# ADDR_ADDR_1.net
KiCad netlist of a schematic drawn in EAGLE
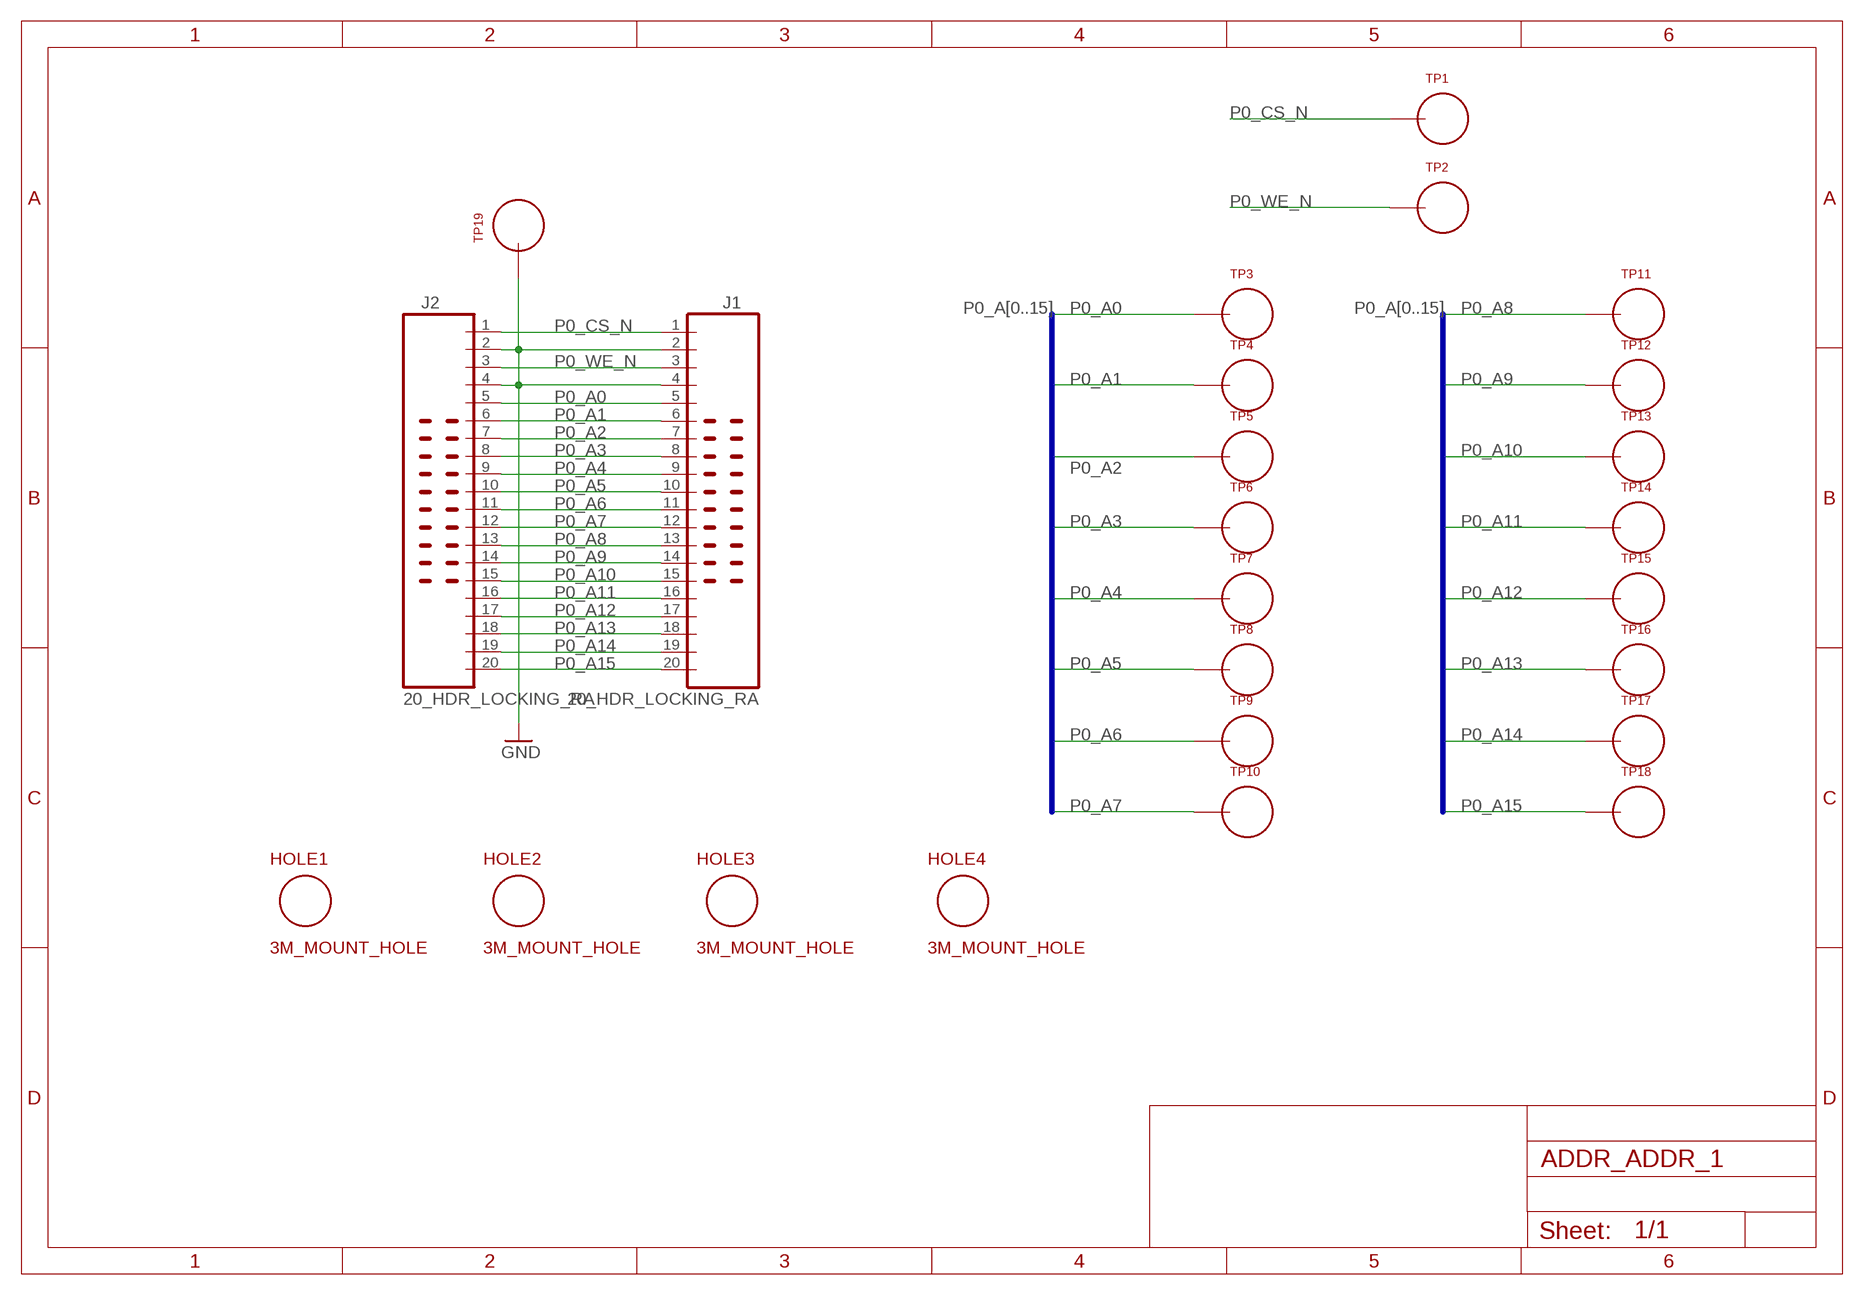
[diagram p0: schematic, sheet 1]

(export (version "E")
  (design (tool "Eeschema 10.0.6"))
  (components
    (comp (ref "HOLE1")
      (value "3M_MOUNT_HOLE")
      (footprint "eagle-import:3M_HOLE")
      (libsource (lib "eagle-import") (part "3M_MOUNT_HOLE"))
    )
    (comp (ref "HOLE2")
      (value "3M_MOUNT_HOLE")
      (footprint "eagle-import:3M_HOLE")
      (libsource (lib "eagle-import") (part "3M_MOUNT_HOLE"))
    )
    (comp (ref "HOLE3")
      (value "3M_MOUNT_HOLE")
      (footprint "eagle-import:3M_HOLE")
      (libsource (lib "eagle-import") (part "3M_MOUNT_HOLE"))
    )
    (comp (ref "HOLE4")
      (value "3M_MOUNT_HOLE")
      (footprint "eagle-import:3M_HOLE")
      (libsource (lib "eagle-import") (part "3M_MOUNT_HOLE"))
    )
    (comp (ref "J1")
      (value "20_HDR_LOCKING_RA")
      (footprint "eagle-import:20_HDR_LOCKING_RA")
      (libsource (lib "eagle-import") (part "20_HDR_LOCKING_RA"))
    )
    (comp (ref "J2")
      (value "20_HDR_LOCKING_RA")
      (footprint "eagle-import:20_HDR_LOCKING_RA")
      (libsource (lib "eagle-import") (part "20_HDR_LOCKING_RA"))
    )
    (comp (ref "TP1")
      (value "TEST_LOOP")
      (footprint "eagle-import:TEST_LOOP")
      (libsource (lib "eagle-import") (part "TEST_LOOP"))
    )
    (comp (ref "TP2")
      (value "TEST_LOOP")
      (footprint "eagle-import:TEST_LOOP")
      (libsource (lib "eagle-import") (part "TEST_LOOP"))
    )
    (comp (ref "TP3")
      (value "TEST_LOOP")
      (footprint "eagle-import:TEST_LOOP")
      (libsource (lib "eagle-import") (part "TEST_LOOP"))
    )
    (comp (ref "TP4")
      (value "TEST_LOOP")
      (footprint "eagle-import:TEST_LOOP")
      (libsource (lib "eagle-import") (part "TEST_LOOP"))
    )
    (comp (ref "TP5")
      (value "TEST_LOOP")
      (footprint "eagle-import:TEST_LOOP")
      (libsource (lib "eagle-import") (part "TEST_LOOP"))
    )
    (comp (ref "TP6")
      (value "TEST_LOOP")
      (footprint "eagle-import:TEST_LOOP")
      (libsource (lib "eagle-import") (part "TEST_LOOP"))
    )
    (comp (ref "TP7")
      (value "TEST_LOOP")
      (footprint "eagle-import:TEST_LOOP")
      (libsource (lib "eagle-import") (part "TEST_LOOP"))
    )
    (comp (ref "TP8")
      (value "TEST_LOOP")
      (footprint "eagle-import:TEST_LOOP")
      (libsource (lib "eagle-import") (part "TEST_LOOP"))
    )
    (comp (ref "TP9")
      (value "TEST_LOOP")
      (footprint "eagle-import:TEST_LOOP")
      (libsource (lib "eagle-import") (part "TEST_LOOP"))
    )
    (comp (ref "TP10")
      (value "TEST_LOOP")
      (footprint "eagle-import:TEST_LOOP")
      (libsource (lib "eagle-import") (part "TEST_LOOP"))
    )
    (comp (ref "TP11")
      (value "TEST_LOOP")
      (footprint "eagle-import:TEST_LOOP")
      (libsource (lib "eagle-import") (part "TEST_LOOP"))
    )
    (comp (ref "TP12")
      (value "TEST_LOOP")
      (footprint "eagle-import:TEST_LOOP")
      (libsource (lib "eagle-import") (part "TEST_LOOP"))
    )
    (comp (ref "TP13")
      (value "TEST_LOOP")
      (footprint "eagle-import:TEST_LOOP")
      (libsource (lib "eagle-import") (part "TEST_LOOP"))
    )
    (comp (ref "TP14")
      (value "TEST_LOOP")
      (footprint "eagle-import:TEST_LOOP")
      (libsource (lib "eagle-import") (part "TEST_LOOP"))
    )
    (comp (ref "TP15")
      (value "TEST_LOOP")
      (footprint "eagle-import:TEST_LOOP")
      (libsource (lib "eagle-import") (part "TEST_LOOP"))
    )
    (comp (ref "TP16")
      (value "TEST_LOOP")
      (footprint "eagle-import:TEST_LOOP")
      (libsource (lib "eagle-import") (part "TEST_LOOP"))
    )
    (comp (ref "TP17")
      (value "TEST_LOOP")
      (footprint "eagle-import:TEST_LOOP")
      (libsource (lib "eagle-import") (part "TEST_LOOP"))
    )
    (comp (ref "TP18")
      (value "TEST_LOOP")
      (footprint "eagle-import:TEST_LOOP")
      (libsource (lib "eagle-import") (part "TEST_LOOP"))
    )
    (comp (ref "TP19")
      (value "TEST_LOOP")
      (footprint "eagle-import:TEST_LOOP")
      (libsource (lib "eagle-import") (part "TEST_LOOP"))
    )
  )
  (nets
    (net (code "1") (name "/P0_A0") (class "Default")
      (node (ref "J1") (pin "5") (pinfunction "5_5") (pintype "bidirectional"))
      (node (ref "J2") (pin "5") (pinfunction "5_5") (pintype "bidirectional"))
      (node (ref "TP3") (pin "P$1") (pinfunction "P$1_P$1") (pintype "bidirectional"))
    )
    (net (code "2") (name "/P0_A1") (class "Default")
      (node (ref "J1") (pin "6") (pinfunction "6_6") (pintype "bidirectional"))
      (node (ref "J2") (pin "6") (pinfunction "6_6") (pintype "bidirectional"))
      (node (ref "TP4") (pin "P$1") (pinfunction "P$1_P$1") (pintype "bidirectional"))
    )
    (net (code "3") (name "/P0_A2") (class "Default")
      (node (ref "J1") (pin "7") (pinfunction "7_7") (pintype "bidirectional"))
      (node (ref "J2") (pin "7") (pinfunction "7_7") (pintype "bidirectional"))
      (node (ref "TP5") (pin "P$1") (pinfunction "P$1_P$1") (pintype "bidirectional"))
    )
    (net (code "4") (name "/P0_A3") (class "Default")
      (node (ref "J1") (pin "8") (pinfunction "8_8") (pintype "bidirectional"))
      (node (ref "J2") (pin "8") (pinfunction "8_8") (pintype "bidirectional"))
      (node (ref "TP6") (pin "P$1") (pinfunction "P$1_P$1") (pintype "bidirectional"))
    )
    (net (code "5") (name "/P0_A4") (class "Default")
      (node (ref "J1") (pin "9") (pinfunction "9_9") (pintype "bidirectional"))
      (node (ref "J2") (pin "9") (pinfunction "9_9") (pintype "bidirectional"))
      (node (ref "TP7") (pin "P$1") (pinfunction "P$1_P$1") (pintype "bidirectional"))
    )
    (net (code "6") (name "/P0_A5") (class "Default")
      (node (ref "J1") (pin "10") (pinfunction "10_10") (pintype "bidirectional"))
      (node (ref "J2") (pin "10") (pinfunction "10_10") (pintype "bidirectional"))
      (node (ref "TP8") (pin "P$1") (pinfunction "P$1_P$1") (pintype "bidirectional"))
    )
    (net (code "7") (name "/P0_A6") (class "Default")
      (node (ref "J1") (pin "11") (pinfunction "11_11") (pintype "bidirectional"))
      (node (ref "J2") (pin "11") (pinfunction "11_11") (pintype "bidirectional"))
      (node (ref "TP9") (pin "P$1") (pinfunction "P$1_P$1") (pintype "bidirectional"))
    )
    (net (code "8") (name "/P0_A7") (class "Default")
      (node (ref "J1") (pin "12") (pinfunction "12_12") (pintype "bidirectional"))
      (node (ref "J2") (pin "12") (pinfunction "12_12") (pintype "bidirectional"))
      (node (ref "TP10") (pin "P$1") (pinfunction "P$1_P$1") (pintype "bidirectional"))
    )
    (net (code "9") (name "/P0_A8") (class "Default")
      (node (ref "J1") (pin "13") (pinfunction "13_13") (pintype "bidirectional"))
      (node (ref "J2") (pin "13") (pinfunction "13_13") (pintype "bidirectional"))
      (node (ref "TP11") (pin "P$1") (pinfunction "P$1_P$1") (pintype "bidirectional"))
    )
    (net (code "10") (name "/P0_A9") (class "Default")
      (node (ref "J1") (pin "14") (pinfunction "14_14") (pintype "bidirectional"))
      (node (ref "J2") (pin "14") (pinfunction "14_14") (pintype "bidirectional"))
      (node (ref "TP12") (pin "P$1") (pinfunction "P$1_P$1") (pintype "bidirectional"))
    )
    (net (code "11") (name "/P0_A10") (class "Default")
      (node (ref "J1") (pin "15") (pinfunction "15_15") (pintype "bidirectional"))
      (node (ref "J2") (pin "15") (pinfunction "15_15") (pintype "bidirectional"))
      (node (ref "TP13") (pin "P$1") (pinfunction "P$1_P$1") (pintype "bidirectional"))
    )
    (net (code "12") (name "/P0_A11") (class "Default")
      (node (ref "J1") (pin "16") (pinfunction "16_16") (pintype "bidirectional"))
      (node (ref "J2") (pin "16") (pinfunction "16_16") (pintype "bidirectional"))
      (node (ref "TP14") (pin "P$1") (pinfunction "P$1_P$1") (pintype "bidirectional"))
    )
    (net (code "13") (name "/P0_A12") (class "Default")
      (node (ref "J1") (pin "17") (pinfunction "17_17") (pintype "bidirectional"))
      (node (ref "J2") (pin "17") (pinfunction "17_17") (pintype "bidirectional"))
      (node (ref "TP15") (pin "P$1") (pinfunction "P$1_P$1") (pintype "bidirectional"))
    )
    (net (code "14") (name "/P0_A13") (class "Default")
      (node (ref "J1") (pin "18") (pinfunction "18_18") (pintype "bidirectional"))
      (node (ref "J2") (pin "18") (pinfunction "18_18") (pintype "bidirectional"))
      (node (ref "TP16") (pin "P$1") (pinfunction "P$1_P$1") (pintype "bidirectional"))
    )
    (net (code "15") (name "/P0_A14") (class "Default")
      (node (ref "J1") (pin "19") (pinfunction "19_19") (pintype "bidirectional"))
      (node (ref "J2") (pin "19") (pinfunction "19_19") (pintype "bidirectional"))
      (node (ref "TP17") (pin "P$1") (pinfunction "P$1_P$1") (pintype "bidirectional"))
    )
    (net (code "16") (name "/P0_A15") (class "Default")
      (node (ref "J1") (pin "20") (pinfunction "20_20") (pintype "bidirectional"))
      (node (ref "J2") (pin "20") (pinfunction "20_20") (pintype "bidirectional"))
      (node (ref "TP18") (pin "P$1") (pinfunction "P$1_P$1") (pintype "bidirectional"))
    )
    (net (code "18") (name "/P0_CS_N") (class "Default")
      (node (ref "J1") (pin "1") (pinfunction "1_1") (pintype "bidirectional"))
      (node (ref "J2") (pin "1") (pinfunction "1_1") (pintype "bidirectional"))
      (node (ref "TP1") (pin "P$1") (pinfunction "P$1_P$1") (pintype "bidirectional"))
    )
    (net (code "19") (name "/P0_WE_N") (class "Default")
      (node (ref "J1") (pin "3") (pinfunction "3_3") (pintype "bidirectional"))
      (node (ref "J2") (pin "3") (pinfunction "3_3") (pintype "bidirectional"))
      (node (ref "TP2") (pin "P$1") (pinfunction "P$1_P$1") (pintype "bidirectional"))
    )
    (net (code "20") (name "GND") (class "Default")
      (node (ref "J1") (pin "2") (pinfunction "2_2") (pintype "bidirectional"))
      (node (ref "J1") (pin "4") (pinfunction "4_4") (pintype "bidirectional"))
      (node (ref "J2") (pin "2") (pinfunction "2_2") (pintype "bidirectional"))
      (node (ref "J2") (pin "4") (pinfunction "4_4") (pintype "bidirectional"))
      (node (ref "TP19") (pin "P$1") (pinfunction "P$1_P$1") (pintype "bidirectional"))
    )
  )
)
